# Radio.net
KiCad netlist of a schematic drawn in Altium Designer
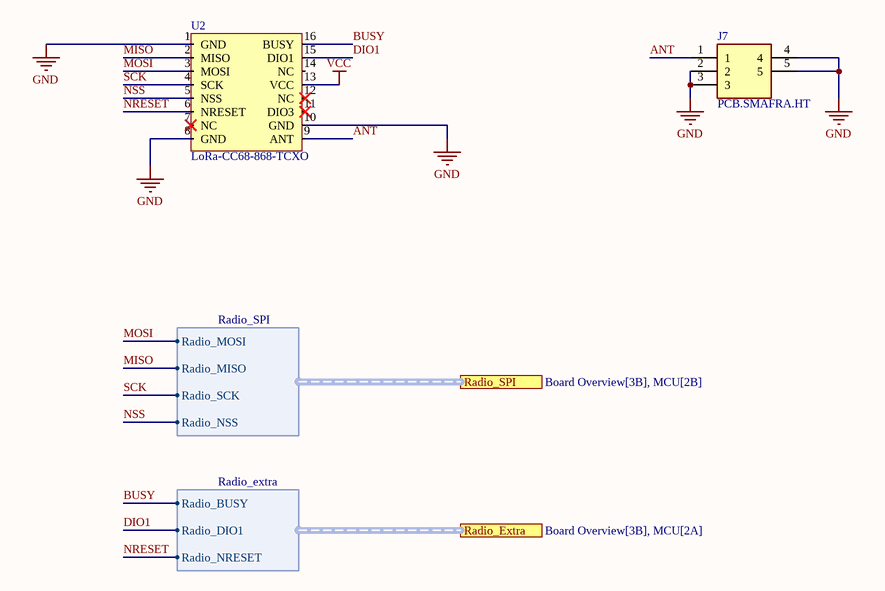
[diagram p0: Radio.SchDoc]

(export (version "E")
  (design (tool "Eeschema 10.0.6"))
  (components
    (comp (ref "J7")
      (value "PCB.SMAFRA.HT")
      (footprint "PCBSMAFRAHT")
      (description "RF Connectors / Coaxial Connectors SMA RA PCB Mount, Jack, Gold, 50 , Through Hole Pin")
      (fields (field (name "MOUSER PART NUMBER") "960-PCB.SMAFRA.HT"))
      (libsource (lib "StrathSEDS") (part "PCB.SMAFRA.HT"))
    )
    (comp (ref "U2")
      (value "LoRa-CC68-868-TCXO")
      (footprint "LoRa-CC68-868-TCXO-Footprint-1")
      (description "LoRa-CC68 targeting 868MHz and with a TXCO")
      (libsource (lib "StrathSEDS") (part "LoRa-CC68-868-TCXO-Symbol-1"))
    )
  )
  (nets
    (net (code "3") (name "/ANT") (class "Default")
      (node (ref "J7") (pin "1") (pinfunction "1_1") (pintype "passive"))
      (node (ref "U2") (pin "9") (pinfunction "ANT_9") (pintype "output"))
    )
    (net (code "4") (name "/BUSY") (class "Default")
      (node (ref "U2") (pin "16") (pinfunction "BUSY_16") (pintype "output"))
    )
    (net (code "5") (name "/DIO1") (class "Default")
      (node (ref "U2") (pin "15") (pinfunction "DIO1_15") (pintype "output"))
    )
    (net (code "6") (name "/MISO") (class "Default")
      (node (ref "U2") (pin "2") (pinfunction "MISO_2") (pintype "output"))
    )
    (net (code "7") (name "/MOSI") (class "Default")
      (node (ref "U2") (pin "3") (pinfunction "MOSI_3") (pintype "input"))
    )
    (net (code "8") (name "/NRESET") (class "Default")
      (node (ref "U2") (pin "6") (pinfunction "NRESET_6") (pintype "input"))
    )
    (net (code "9") (name "/NSS") (class "Default")
      (node (ref "U2") (pin "5") (pinfunction "NSS_5") (pintype "input"))
    )
    (net (code "10") (name "/SCK") (class "Default")
      (node (ref "U2") (pin "4") (pinfunction "SCK_4") (pintype "input"))
    )
    (net (code "13") (name "GND") (class "Default")
      (node (ref "J7") (pin "2") (pinfunction "2_2") (pintype "passive"))
      (node (ref "J7") (pin "3") (pinfunction "3_3") (pintype "passive"))
      (node (ref "J7") (pin "4") (pinfunction "4_4") (pintype "passive"))
      (node (ref "J7") (pin "5") (pinfunction "5_5") (pintype "passive"))
      (node (ref "U2") (pin "1") (pinfunction "GND_1") (pintype "power_in"))
      (node (ref "U2") (pin "10") (pinfunction "GND_10") (pintype "input"))
      (node (ref "U2") (pin "8") (pinfunction "GND_8") (pintype "power_in"))
    )
    (net (code "14") (name "VCC") (class "Default")
      (node (ref "U2") (pin "13") (pinfunction "VCC_13") (pintype "power_in"))
    )
    (net (code "15") (name "unconnected-(U2-DIO3-Pad11)") (class "Default")
      (node (ref "U2") (pin "11") (pinfunction "DIO3_11") (pintype "output+no_connect"))
    )
    (net (code "16") (name "unconnected-(U2-NC-Pad7)") (class "Default")
      (node (ref "U2") (pin "7") (pinfunction "NC_7") (pintype "passive+no_connect"))
    )
    (net (code "17") (name "unconnected-(U2-NC-Pad12)") (class "Default")
      (node (ref "U2") (pin "12") (pinfunction "NC_12") (pintype "passive+no_connect"))
    )
    (net (code "18") (name "unconnected-(U2-NC-Pad14)") (class "Default")
      (node (ref "U2") (pin "14") (pinfunction "NC_14") (pintype "passive"))
    )
  )
)
